# Visual_User_Interface.net
KiCad netlist of a schematic drawn in Altium Designer
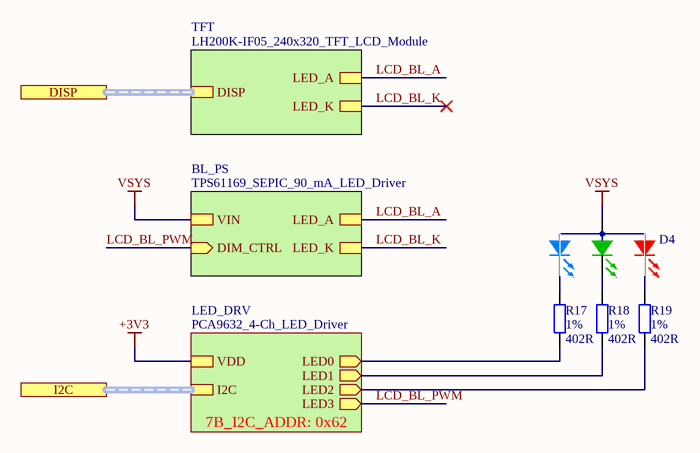
[diagram p0: Visual_User_Interface.SchDoc]

(export (version "E")
  (design (tool "Eeschema 10.0.6"))
  (components
    (comp (ref "D4")
      (value "150066M153000")
      (footprint "LED_0606_RGB_WURTH")
      (fields (field (name "MANUFACTURER") "Wurth Electronics"))
      (libsource (lib "BLDC_Motor_Driver") (part "LED RGB DIFFUSED SMD"))
    )
    (comp (ref "R17")
      (value "RES SMD 402 OHM 1% 1/16W 0402")
      (footprint "R_0402")
      (description "402 Ohms ±1% 0.063W, 1/16W Chip Resistor 0402 (1005 Metric) Moisture Resistant Thick Film")
      (fields
        (field (name "TOLERANCE") "1%")
        (field (name "MANUFACTURER") "Yageo")
        (field (name "MANUFACTURER PART NUMBER") "RC0402FR-07402RL")
        (field (name "RESISTANCE") "402R")
      )
      (libsource (lib "resistors_smd") (part "RES SMD 402 OHM 1% 1/16W 0402"))
    )
    (comp (ref "R18")
      (value "RES SMD 402 OHM 1% 1/16W 0402")
      (footprint "R_0402")
      (description "402 Ohms ±1% 0.063W, 1/16W Chip Resistor 0402 (1005 Metric) Moisture Resistant Thick Film")
      (fields
        (field (name "TOLERANCE") "1%")
        (field (name "MANUFACTURER") "Yageo")
        (field (name "MANUFACTURER PART NUMBER") "RC0402FR-07402RL")
        (field (name "RESISTANCE") "402R")
      )
      (libsource (lib "resistors_smd") (part "RES SMD 402 OHM 1% 1/16W 0402"))
    )
    (comp (ref "R19")
      (value "RES SMD 402 OHM 1% 1/16W 0402")
      (footprint "R_0402")
      (description "402 Ohms ±1% 0.063W, 1/16W Chip Resistor 0402 (1005 Metric) Moisture Resistant Thick Film")
      (fields
        (field (name "TOLERANCE") "1%")
        (field (name "MANUFACTURER") "Yageo")
        (field (name "MANUFACTURER PART NUMBER") "RC0402FR-07402RL")
        (field (name "RESISTANCE") "402R")
      )
      (libsource (lib "resistors_smd") (part "RES SMD 402 OHM 1% 1/16W 0402"))
    )
  )
  (nets
    (net (code "9") (name "/LED0") (class "Default")
      (node (ref "R17") (pin "1") (pinfunction "1_1") (pintype "passive"))
    )
    (net (code "10") (name "/LED1") (class "Default")
      (node (ref "R18") (pin "1") (pinfunction "1_1") (pintype "passive"))
    )
    (net (code "11") (name "/LED2") (class "Default")
      (node (ref "R19") (pin "1") (pinfunction "1_1") (pintype "passive"))
    )
    (net (code "12") (name "Net-(D4-PadBK)") (class "Default")
      (node (ref "D4") (pin "BK") (pinfunction "BK_BK") (pintype "passive"))
      (node (ref "R17") (pin "2") (pinfunction "2_2") (pintype "passive"))
    )
    (net (code "13") (name "Net-(D4-PadGK)") (class "Default")
      (node (ref "D4") (pin "GK") (pinfunction "GK_GK") (pintype "passive"))
      (node (ref "R18") (pin "2") (pinfunction "2_2") (pintype "passive"))
    )
    (net (code "14") (name "Net-(D4-PadRK)") (class "Default")
      (node (ref "D4") (pin "RK") (pinfunction "RK_RK") (pintype "passive"))
      (node (ref "R19") (pin "2") (pinfunction "2_2") (pintype "passive"))
    )
    (net (code "15") (name "VSYS") (class "Default")
      (node (ref "D4") (pin "A") (pinfunction "A_A") (pintype "passive"))
    )
  )
)
